# USB_PHY.net
KiCad netlist of a schematic drawn in Altium Designer
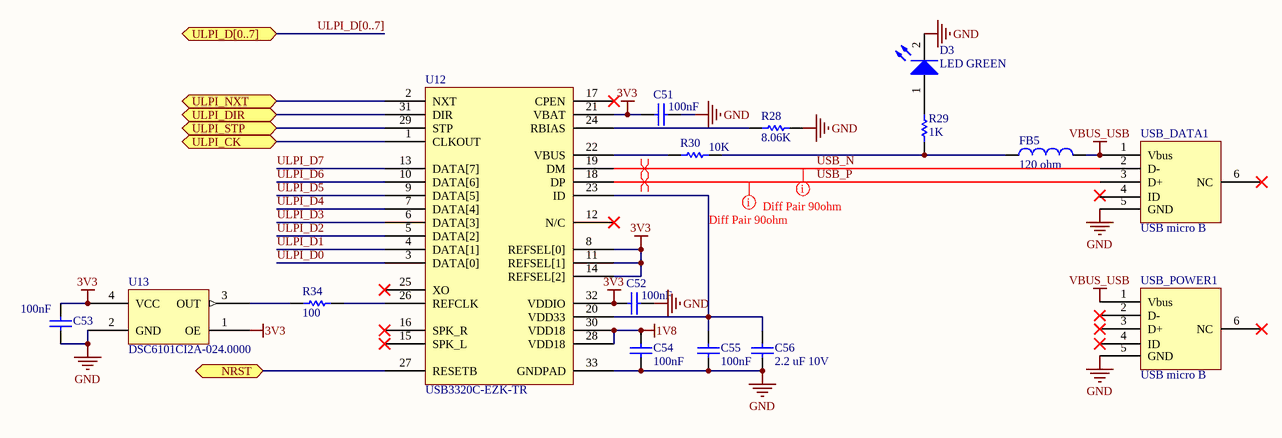
[diagram p0: USB PHY.SchDoc]

(export (version "E")
  (design (tool "Eeschema 10.0.6"))
  (components
    (comp (ref "C51")
      (value "100nF")
      (footprint "0603 Cap")
      (description "CAP CER 0.1UF 16V X7R 0603")
      (fields
        (field (name "MANUFACTURER") "KEMET")
        (field (name "MANUFACTURER PART NUMBER") "C0603C104K4RACTU")
      )
      (libsource (lib "Componentes_base") (part "C0603C104K4RACTU"))
    )
    (comp (ref "C52")
      (value "100nF")
      (footprint "0603 Cap")
      (description "CAP CER 0.1UF 16V X7R 0603")
      (fields
        (field (name "MANUFACTURER") "KEMET")
        (field (name "MANUFACTURER PART NUMBER") "C0603C104K4RACTU")
      )
      (libsource (lib "Componentes_base") (part "C0603C104K4RACTU"))
    )
    (comp (ref "C53")
      (value "100nF")
      (footprint "0603 Cap")
      (description "CAP CER 0.1UF 16V X7R 0603")
      (fields
        (field (name "MANUFACTURER") "KEMET")
        (field (name "MANUFACTURER PART NUMBER") "C0603C104K4RACTU")
      )
      (libsource (lib "Componentes_base") (part "C0603C104K4RACTU"))
    )
    (comp (ref "C54")
      (value "100nF")
      (footprint "0603 Cap")
      (description "CAP CER 0.1UF 16V X7R 0603")
      (fields
        (field (name "MANUFACTURER") "KEMET")
        (field (name "MANUFACTURER PART NUMBER") "C0603C104K4RACTU")
      )
      (libsource (lib "Componentes_base") (part "C0603C104K4RACTU"))
    )
    (comp (ref "C55")
      (value "100nF")
      (footprint "0603 Cap")
      (description "CAP CER 0.1UF 16V X7R 0603")
      (fields
        (field (name "MANUFACTURER") "KEMET")
        (field (name "MANUFACTURER PART NUMBER") "C0603C104K4RACTU")
      )
      (libsource (lib "Componentes_base") (part "C0603C104K4RACTU"))
    )
    (comp (ref "C56")
      (value "2.2 uF 10V")
      (footprint "0603 Cap")
      (description "CAP CER 2.2UF 10V X7R 0603")
      (fields
        (field (name "MANUFACTURER") "Samsung Electro-Mechanics America, Inc.")
        (field (name "MANUFACTURER PART NUMBER") "CL10B225KP8NNNC")
      )
      (libsource (lib "Componentes_base") (part "CL10B225KP8NNNC"))
    )
    (comp (ref "D3")
      (value "LED GREEN")
      (footprint "0603 LED")
      (description "LED GREEN CLEAR 0603 SMD")
      (fields
        (field (name "MANUFACTURER") "Lite-On Inc.")
        (field (name "MANUFACTURER PART NUMBER") "LTST-C191KGKT")
      )
      (libsource (lib "Componentes_base") (part "LTST-C191KGKT"))
    )
    (comp (ref "FB5")
      (value "120 ohm")
      (footprint "INDC1608X08L")
      (description "FERRITE BEAD 120 OHM 0603 1LN")
      (fields
        (field (name "MANUFACTURER") "Murata Electronics North America")
        (field (name "MANUFACTURER PART NUMBER") "BLM18PG121SN1D")
      )
      (libsource (lib "Componentes_base") (part "BLM18PG121SN1D"))
    )
    (comp (ref "R28")
      (value "8.06K")
      (footprint "0603 Res")
      (description "RES SMD 8.06K OHM 1% 1/10W 0603")
      (fields
        (field (name "MANUFACTURER") "Yageo")
        (field (name "MANUFACTURER PART NUMBER") "RC0603FR-078K06L")
      )
      (libsource (lib "Componentes_base") (part "RC0603FR-078K06L"))
    )
    (comp (ref "R29")
      (value "1K")
      (footprint "0603 Res")
      (description "RES SMD 1K OHM 1% 1/10W 0603")
      (fields
        (field (name "MANUFACTURER") "Yageo")
        (field (name "MANUFACTURER PART NUMBER") "RC0603FR-071KL")
      )
      (libsource (lib "Componentes_base") (part "RC0603FR-071KL"))
    )
    (comp (ref "R30")
      (value "10K")
      (footprint "0603 Res")
      (description "RES SMD 10K OHM 1% 1/10W 0603")
      (fields
        (field (name "MANUFACTURER") "Yageo")
        (field (name "MANUFACTURER PART NUMBER") "RC0603FR-0710KL")
      )
      (libsource (lib "Componentes_base") (part "RC0603FR-0710KL"))
    )
    (comp (ref "R34")
      (value "100")
      (footprint "RESC1005X04L")
      (description "RES 100 OHM 1/16W 1% 0402 SMD")
      (fields
        (field (name "MANUFACTURER") "Rohm Semiconductor")
        (field (name "MANUFACTURER PART NUMBER") "MCR01MRTF1000")
      )
      (libsource (lib "Componentes_base") (part "MCR01MRTF1000"))
    )
    (comp (ref "U12")
      (value "USB3320C-EZK-TR")
      (footprint "QFN127P600-8N")
      (description "IC TXRX USB 2.0 FLEXPWR 32QFN")
      (fields (field (name "MANUFACTURER") "Microchip Technology"))
      (libsource (lib "Componentes_base") (part "USB3320C-EZK-TR"))
    )
    (comp (ref "U13")
      (value "DSC6101CI2A-024.0000")
      (footprint "DFN 3.2x2.5")
      (description "ULTRA-LOW POWER,MEMS OSCILLATOR,")
      (fields (field (name "MANUFACTURER") "Microchip Technology"))
      (libsource (lib "Componentes_base") (part "DSC6101CI2A-024.0000"))
    )
    (comp (ref "USB_DATA1")
      (value "USB micro B")
      (footprint "USB-MicroB")
      (libsource (lib "B105connectors") (part "USB micro B"))
    )
    (comp (ref "USB_POWER1")
      (value "USB micro B")
      (footprint "USB-MicroB")
      (libsource (lib "B105connectors") (part "USB micro B"))
    )
  )
  (nets
    (net (code "1") (name "/NRST") (class "Default")
      (node (ref "U12") (pin "27") (pinfunction "RESETB_27") (pintype "passive"))
    )
    (net (code "2") (name "/ULPI_CK") (class "Default")
      (node (ref "U12") (pin "1") (pinfunction "CLKOUT_1") (pintype "passive"))
    )
    (net (code "3") (name "/ULPI_D0") (class "Default")
      (node (ref "U12") (pin "3") (pinfunction "DATA[0]_3") (pintype "passive"))
    )
    (net (code "4") (name "/ULPI_D1") (class "Default")
      (node (ref "U12") (pin "4") (pinfunction "DATA[1]_4") (pintype "passive"))
    )
    (net (code "5") (name "/ULPI_D2") (class "Default")
      (node (ref "U12") (pin "5") (pinfunction "DATA[2]_5") (pintype "passive"))
    )
    (net (code "6") (name "/ULPI_D3") (class "Default")
      (node (ref "U12") (pin "6") (pinfunction "DATA[3]_6") (pintype "passive"))
    )
    (net (code "7") (name "/ULPI_D4") (class "Default")
      (node (ref "U12") (pin "7") (pinfunction "DATA[4]_7") (pintype "passive"))
    )
    (net (code "8") (name "/ULPI_D5") (class "Default")
      (node (ref "U12") (pin "9") (pinfunction "DATA[5]_9") (pintype "passive"))
    )
    (net (code "9") (name "/ULPI_D6") (class "Default")
      (node (ref "U12") (pin "10") (pinfunction "DATA[6]_10") (pintype "passive"))
    )
    (net (code "10") (name "/ULPI_D7") (class "Default")
      (node (ref "U12") (pin "13") (pinfunction "DATA[7]_13") (pintype "passive"))
    )
    (net (code "11") (name "/ULPI_DIR") (class "Default")
      (node (ref "U12") (pin "31") (pinfunction "DIR_31") (pintype "passive"))
    )
    (net (code "13") (name "/ULPI_NXT") (class "Default")
      (node (ref "U12") (pin "2") (pinfunction "NXT_2") (pintype "passive"))
    )
    (net (code "14") (name "/ULPI_STP") (class "Default")
      (node (ref "U12") (pin "29") (pinfunction "STP_29") (pintype "passive"))
    )
    (net (code "15") (name "/USB_N") (class "Default")
      (node (ref "U12") (pin "19") (pinfunction "DM_19") (pintype "passive"))
      (node (ref "USB_DATA1") (pin "2") (pinfunction "D-_2") (pintype "passive"))
    )
    (net (code "16") (name "/USB_P") (class "Default")
      (node (ref "U12") (pin "18") (pinfunction "DP_18") (pintype "passive"))
      (node (ref "USB_DATA1") (pin "3") (pinfunction "D+_3") (pintype "passive"))
    )
    (net (code "17") (name "1V8") (class "Default")
      (node (ref "C54") (pin "2") (pinfunction "2_2") (pintype "passive"))
      (node (ref "U12") (pin "28") (pinfunction "VDD18_28") (pintype "passive"))
      (node (ref "U12") (pin "30") (pinfunction "VDD18_30") (pintype "passive"))
    )
    (net (code "18") (name "3V3") (class "Default")
      (node (ref "C51") (pin "2") (pinfunction "2_2") (pintype "passive"))
      (node (ref "C52") (pin "2") (pinfunction "2_2") (pintype "passive"))
      (node (ref "C53") (pin "2") (pinfunction "2_2") (pintype "passive"))
      (node (ref "U12") (pin "11") (pinfunction "REFSEL[1]_11") (pintype "passive"))
      (node (ref "U12") (pin "14") (pinfunction "REFSEL[2]_14") (pintype "passive"))
      (node (ref "U12") (pin "21") (pinfunction "VBAT_21") (pintype "passive"))
      (node (ref "U12") (pin "32") (pinfunction "VDDIO_32") (pintype "passive"))
      (node (ref "U12") (pin "8") (pinfunction "REFSEL[0]_8") (pintype "passive"))
      (node (ref "U13") (pin "1") (pinfunction "OE_1") (pintype "passive"))
      (node (ref "U13") (pin "4") (pinfunction "VCC_4") (pintype "power_in"))
    )
    (net (code "19") (name "GND") (class "Default")
      (node (ref "C51") (pin "1") (pinfunction "1_1") (pintype "passive"))
      (node (ref "C52") (pin "1") (pinfunction "1_1") (pintype "passive"))
      (node (ref "C53") (pin "1") (pinfunction "1_1") (pintype "passive"))
      (node (ref "C54") (pin "1") (pinfunction "1_1") (pintype "passive"))
      (node (ref "C55") (pin "1") (pinfunction "1_1") (pintype "passive"))
      (node (ref "C56") (pin "1") (pinfunction "1_1") (pintype "passive"))
      (node (ref "D3") (pin "2") (pinfunction "C_2") (pintype "passive"))
      (node (ref "R28") (pin "2") (pinfunction "2_2") (pintype "passive"))
      (node (ref "U12") (pin "33") (pinfunction "GNDPAD_33") (pintype "passive"))
      (node (ref "U13") (pin "2") (pinfunction "GND_2") (pintype "power_in"))
      (node (ref "USB_DATA1") (pin "5") (pinfunction "GND_5") (pintype "passive"))
      (node (ref "USB_POWER1") (pin "5") (pinfunction "GND_5") (pintype "passive"))
    )
    (net (code "20") (name "Net-(D3-A)") (class "Default")
      (node (ref "D3") (pin "1") (pinfunction "A_1") (pintype "passive"))
      (node (ref "R29") (pin "2") (pinfunction "2_2") (pintype "passive"))
    )
    (net (code "21") (name "Net-(FB5-Pad1)") (class "Default")
      (node (ref "FB5") (pin "1") (pinfunction "1_1") (pintype "passive"))
      (node (ref "R29") (pin "1") (pinfunction "1_1") (pintype "passive"))
      (node (ref "R30") (pin "2") (pinfunction "2_2") (pintype "passive"))
    )
    (net (code "22") (name "Net-(U12-ID)") (class "Default")
      (node (ref "C55") (pin "2") (pinfunction "2_2") (pintype "passive"))
      (node (ref "C56") (pin "2") (pinfunction "2_2") (pintype "passive"))
      (node (ref "U12") (pin "20") (pinfunction "VDD33_20") (pintype "passive"))
      (node (ref "U12") (pin "23") (pinfunction "ID_23") (pintype "passive"))
    )
    (net (code "23") (name "Net-(U12-RBIAS)") (class "Default")
      (node (ref "R28") (pin "1") (pinfunction "1_1") (pintype "passive"))
      (node (ref "U12") (pin "24") (pinfunction "RBIAS_24") (pintype "passive"))
    )
    (net (code "24") (name "Net-(U12-REFCLK)") (class "Default")
      (node (ref "R34") (pin "2") (pinfunction "2_2") (pintype "passive"))
      (node (ref "U12") (pin "26") (pinfunction "REFCLK_26") (pintype "passive"))
    )
    (net (code "25") (name "Net-(U12-VBUS)") (class "Default")
      (node (ref "R30") (pin "1") (pinfunction "1_1") (pintype "passive"))
      (node (ref "U12") (pin "22") (pinfunction "VBUS_22") (pintype "passive"))
    )
    (net (code "26") (name "Net-(U13-OUT)") (class "Default")
      (node (ref "R34") (pin "1") (pinfunction "1_1") (pintype "passive"))
      (node (ref "U13") (pin "3") (pinfunction "OUT_3") (pintype "output"))
    )
    (net (code "27") (name "VBUS_USB") (class "Default")
      (node (ref "FB5") (pin "2") (pinfunction "2_2") (pintype "passive"))
      (node (ref "USB_DATA1") (pin "1") (pinfunction "Vbus_1") (pintype "passive"))
      (node (ref "USB_POWER1") (pin "1") (pinfunction "Vbus_1") (pintype "passive"))
    )
    (net (code "28") (name "unconnected-(U12-CPEN-Pad17)") (class "Default")
      (node (ref "U12") (pin "17") (pinfunction "CPEN_17") (pintype "passive+no_connect"))
    )
    (net (code "29") (name "unconnected-(U12-N{slash}C-Pad12)") (class "Default")
      (node (ref "U12") (pin "12") (pinfunction "N/C_12") (pintype "passive+no_connect"))
    )
    (net (code "30") (name "unconnected-(U12-SPK_L-Pad15)") (class "Default")
      (node (ref "U12") (pin "15") (pinfunction "SPK_L_15") (pintype "passive+no_connect"))
    )
    (net (code "31") (name "unconnected-(U12-SPK_R-Pad16)") (class "Default")
      (node (ref "U12") (pin "16") (pinfunction "SPK_R_16") (pintype "passive+no_connect"))
    )
    (net (code "32") (name "unconnected-(U12-XO-Pad25)") (class "Default")
      (node (ref "U12") (pin "25") (pinfunction "XO_25") (pintype "passive+no_connect"))
    )
    (net (code "33") (name "unconnected-(USB_DATA1-ID-Pad4)") (class "Default")
      (node (ref "USB_DATA1") (pin "4") (pinfunction "ID_4") (pintype "passive"))
    )
    (net (code "34") (name "unconnected-(USB_DATA1-NC-Pad6)") (class "Default")
      (node (ref "USB_DATA1") (pin "6") (pinfunction "NC_6") (pintype "passive+no_connect"))
    )
    (net (code "35") (name "unconnected-(USB_POWER1-D+-Pad3)") (class "Default")
      (node (ref "USB_POWER1") (pin "3") (pinfunction "D+_3") (pintype "passive+no_connect"))
    )
    (net (code "36") (name "unconnected-(USB_POWER1-D--Pad2)") (class "Default")
      (node (ref "USB_POWER1") (pin "2") (pinfunction "D-_2") (pintype "passive+no_connect"))
    )
    (net (code "37") (name "unconnected-(USB_POWER1-ID-Pad4)") (class "Default")
      (node (ref "USB_POWER1") (pin "4") (pinfunction "ID_4") (pintype "passive+no_connect"))
    )
    (net (code "38") (name "unconnected-(USB_POWER1-NC-Pad6)") (class "Default")
      (node (ref "USB_POWER1") (pin "6") (pinfunction "NC_6") (pintype "passive+no_connect"))
    )
  )
)
